# EXT_ADIN.net
KiCad netlist of a schematic drawn in EAGLE
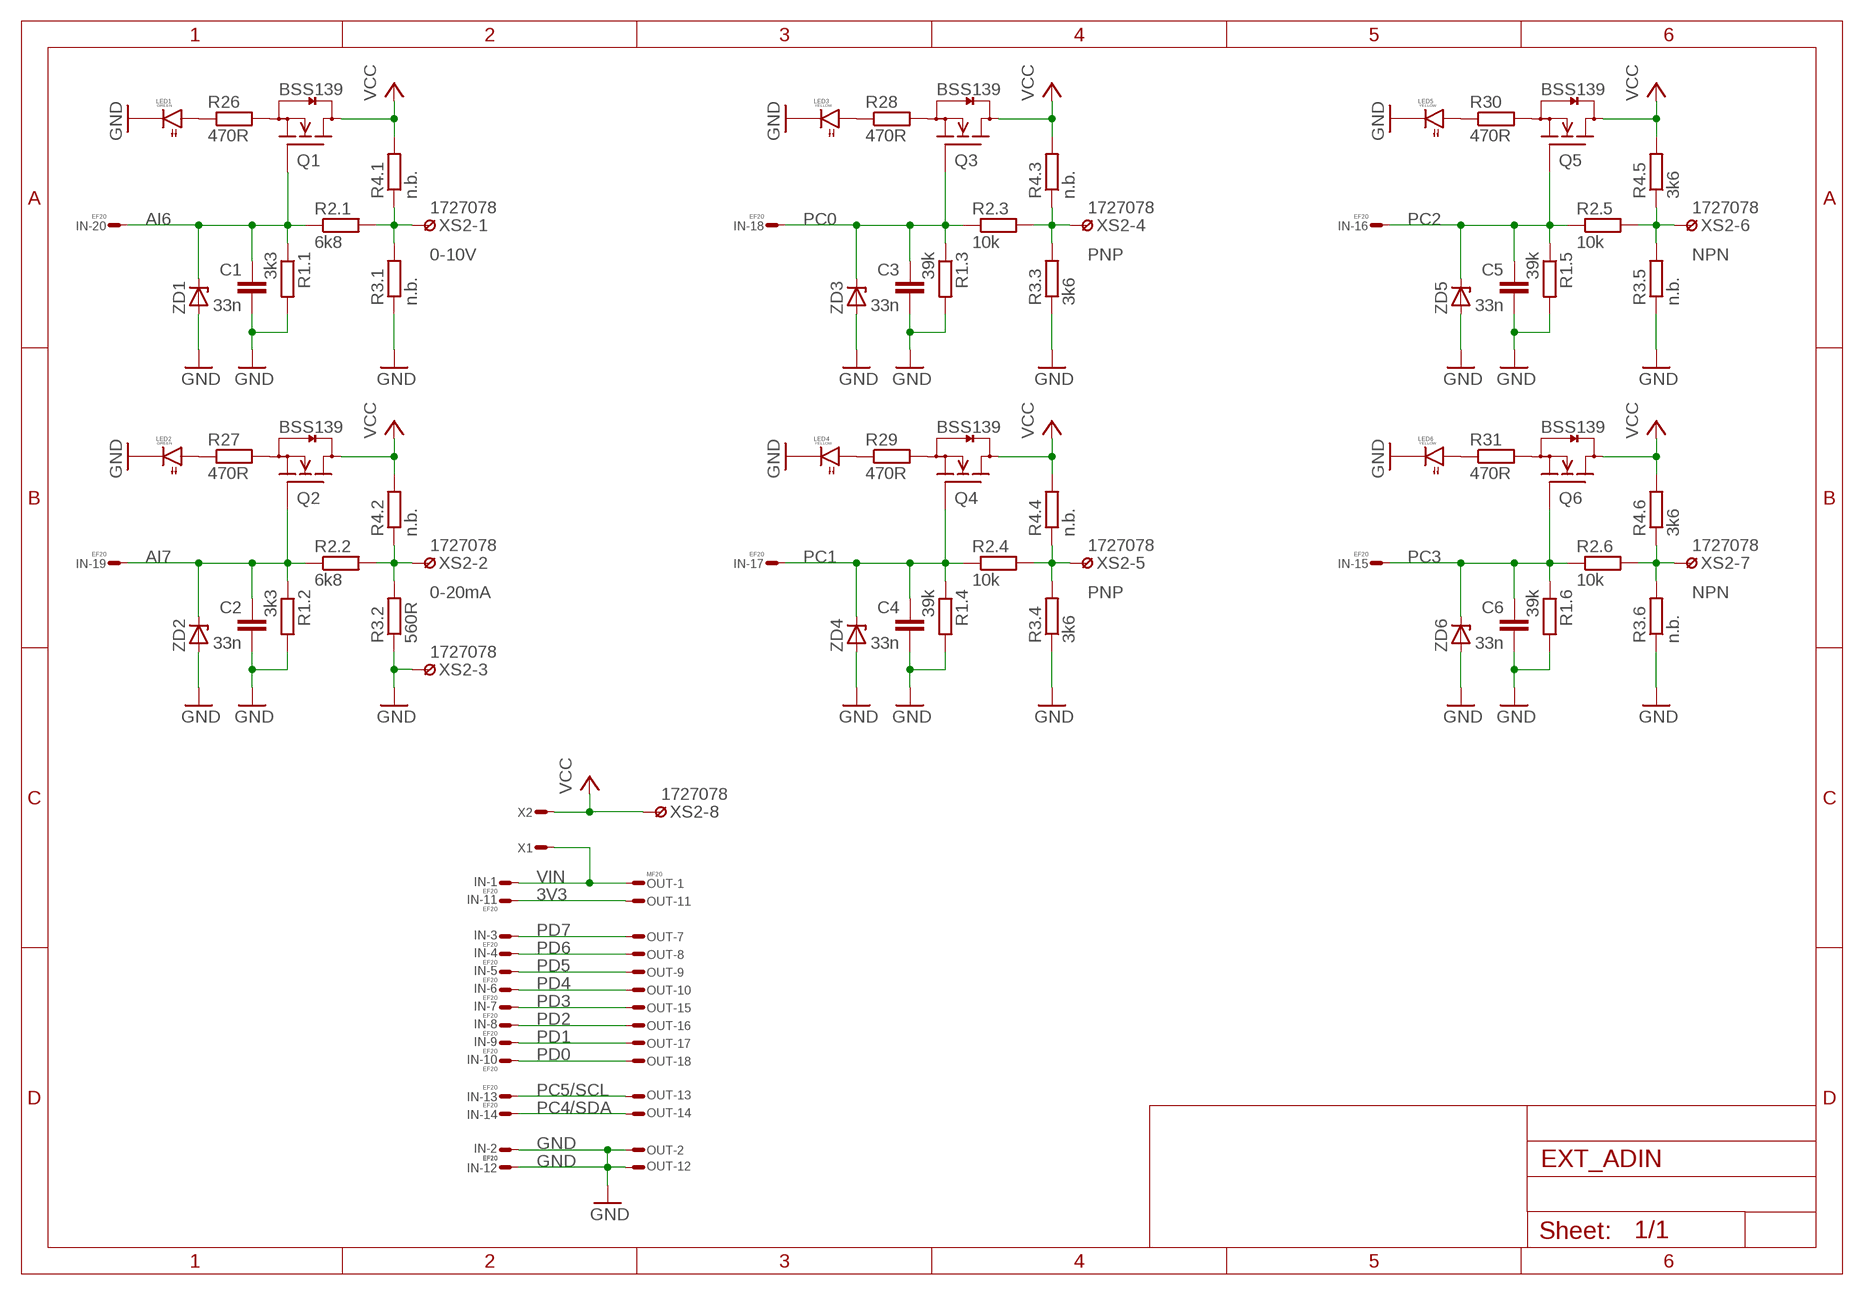
[diagram p0: schematic, sheet 1]

(export (version "E")
  (design (tool "Eeschema 10.0.6"))
  (components
    (comp (ref "C1")
      (value "33n")
      (footprint "eagle-import:1206")
      (libsource (lib "eagle-import") (part "C1206"))
    )
    (comp (ref "C2")
      (value "33n")
      (footprint "eagle-import:1206")
      (libsource (lib "eagle-import") (part "C1206"))
    )
    (comp (ref "C3")
      (value "33n")
      (footprint "eagle-import:1206")
      (libsource (lib "eagle-import") (part "C1206"))
    )
    (comp (ref "C4")
      (value "33n")
      (footprint "eagle-import:1206")
      (libsource (lib "eagle-import") (part "C1206"))
    )
    (comp (ref "C5")
      (value "33n")
      (footprint "eagle-import:1206")
      (libsource (lib "eagle-import") (part "C1206"))
    )
    (comp (ref "C6")
      (value "33n")
      (footprint "eagle-import:1206")
      (libsource (lib "eagle-import") (part "C1206"))
    )
    (comp (ref "IN")
      (value "EF20")
      (footprint "eagle-import:FE10-2WS")
      (libsource (lib "eagle-import") (part "FE20ELS"))
    )
    (comp (ref "LED1")
      (value "GREEN")
      (footprint "eagle-import:1206")
      (libsource (lib "eagle-import") (part "LED1206"))
    )
    (comp (ref "LED2")
      (value "GREEN")
      (footprint "eagle-import:1206")
      (libsource (lib "eagle-import") (part "LED1206"))
    )
    (comp (ref "LED3")
      (value "YELLOW")
      (footprint "eagle-import:1206")
      (libsource (lib "eagle-import") (part "LED1206"))
    )
    (comp (ref "LED4")
      (value "YELLOW")
      (footprint "eagle-import:1206")
      (libsource (lib "eagle-import") (part "LED1206"))
    )
    (comp (ref "LED5")
      (value "YELLOW")
      (footprint "eagle-import:1206")
      (libsource (lib "eagle-import") (part "LED1206"))
    )
    (comp (ref "LED6")
      (value "YELLOW")
      (footprint "eagle-import:1206")
      (libsource (lib "eagle-import") (part "LED1206"))
    )
    (comp (ref "OUT")
      (value "MF20")
      (footprint "eagle-import:ML20LS")
      (libsource (lib "eagle-import") (part "ML20?ELS"))
    )
    (comp (ref "Q1")
      (value "BSS139")
      (footprint "eagle-import:SOT23")
      (libsource (lib "eagle-import") (part "FET-ND23"))
    )
    (comp (ref "Q2")
      (value "BSS139")
      (footprint "eagle-import:SOT23")
      (libsource (lib "eagle-import") (part "FET-ND23"))
    )
    (comp (ref "Q3")
      (value "BSS139")
      (footprint "eagle-import:SOT23")
      (libsource (lib "eagle-import") (part "FET-ND23"))
    )
    (comp (ref "Q4")
      (value "BSS139")
      (footprint "eagle-import:SOT23")
      (libsource (lib "eagle-import") (part "FET-ND23"))
    )
    (comp (ref "Q5")
      (value "BSS139")
      (footprint "eagle-import:SOT23")
      (libsource (lib "eagle-import") (part "FET-ND23"))
    )
    (comp (ref "Q6")
      (value "BSS139")
      (footprint "eagle-import:SOT23")
      (libsource (lib "eagle-import") (part "FET-ND23"))
    )
    (comp (ref "R1.1")
      (value "3k3")
      (footprint "eagle-import:1206")
      (libsource (lib "eagle-import") (part "R1206"))
    )
    (comp (ref "R1.2")
      (value "3k3")
      (footprint "eagle-import:1206")
      (libsource (lib "eagle-import") (part "R1206"))
    )
    (comp (ref "R1.3")
      (value "39k")
      (footprint "eagle-import:1206")
      (libsource (lib "eagle-import") (part "R1206"))
    )
    (comp (ref "R1.4")
      (value "39k")
      (footprint "eagle-import:1206")
      (libsource (lib "eagle-import") (part "R1206"))
    )
    (comp (ref "R1.5")
      (value "39k")
      (footprint "eagle-import:1206")
      (libsource (lib "eagle-import") (part "R1206"))
    )
    (comp (ref "R1.6")
      (value "39k")
      (footprint "eagle-import:1206")
      (libsource (lib "eagle-import") (part "R1206"))
    )
    (comp (ref "R2.1")
      (value "6k8")
      (footprint "eagle-import:1206")
      (libsource (lib "eagle-import") (part "R1206"))
    )
    (comp (ref "R2.2")
      (value "6k8")
      (footprint "eagle-import:1206")
      (libsource (lib "eagle-import") (part "R1206"))
    )
    (comp (ref "R2.3")
      (value "10k")
      (footprint "eagle-import:1206")
      (libsource (lib "eagle-import") (part "R1206"))
    )
    (comp (ref "R2.4")
      (value "10k")
      (footprint "eagle-import:1206")
      (libsource (lib "eagle-import") (part "R1206"))
    )
    (comp (ref "R2.5")
      (value "10k")
      (footprint "eagle-import:1206")
      (libsource (lib "eagle-import") (part "R1206"))
    )
    (comp (ref "R2.6")
      (value "10k")
      (footprint "eagle-import:1206")
      (libsource (lib "eagle-import") (part "R1206"))
    )
    (comp (ref "R3.1")
      (value "n.b.")
      (footprint "eagle-import:1206")
      (libsource (lib "eagle-import") (part "R1206"))
    )
    (comp (ref "R3.2")
      (value "560R")
      (footprint "eagle-import:1206")
      (libsource (lib "eagle-import") (part "R1206"))
    )
    (comp (ref "R3.3")
      (value "3k6")
      (footprint "eagle-import:1206")
      (libsource (lib "eagle-import") (part "R1206"))
    )
    (comp (ref "R3.4")
      (value "3k6")
      (footprint "eagle-import:1206")
      (libsource (lib "eagle-import") (part "R1206"))
    )
    (comp (ref "R3.5")
      (value "n.b.")
      (footprint "eagle-import:1206")
      (libsource (lib "eagle-import") (part "R1206"))
    )
    (comp (ref "R3.6")
      (value "n.b.")
      (footprint "eagle-import:1206")
      (libsource (lib "eagle-import") (part "R1206"))
    )
    (comp (ref "R4.1")
      (value "n.b.")
      (footprint "eagle-import:1206")
      (libsource (lib "eagle-import") (part "R1206"))
    )
    (comp (ref "R4.2")
      (value "n.b.")
      (footprint "eagle-import:1206")
      (libsource (lib "eagle-import") (part "R1206"))
    )
    (comp (ref "R4.3")
      (value "n.b.")
      (footprint "eagle-import:1206")
      (libsource (lib "eagle-import") (part "R1206"))
    )
    (comp (ref "R4.4")
      (value "n.b.")
      (footprint "eagle-import:1206")
      (libsource (lib "eagle-import") (part "R1206"))
    )
    (comp (ref "R4.5")
      (value "3k6")
      (footprint "eagle-import:1206")
      (libsource (lib "eagle-import") (part "R1206"))
    )
    (comp (ref "R4.6")
      (value "3k6")
      (footprint "eagle-import:1206")
      (libsource (lib "eagle-import") (part "R1206"))
    )
    (comp (ref "R26")
      (value "470R")
      (footprint "eagle-import:1206")
      (libsource (lib "eagle-import") (part "R1206"))
    )
    (comp (ref "R27")
      (value "470R")
      (footprint "eagle-import:1206")
      (libsource (lib "eagle-import") (part "R1206"))
    )
    (comp (ref "R28")
      (value "470R")
      (footprint "eagle-import:1206")
      (libsource (lib "eagle-import") (part "R1206"))
    )
    (comp (ref "R29")
      (value "470R")
      (footprint "eagle-import:1206")
      (libsource (lib "eagle-import") (part "R1206"))
    )
    (comp (ref "R30")
      (value "470R")
      (footprint "eagle-import:1206")
      (libsource (lib "eagle-import") (part "R1206"))
    )
    (comp (ref "R31")
      (value "470R")
      (footprint "eagle-import:1206")
      (libsource (lib "eagle-import") (part "R1206"))
    )
    (comp (ref "X1")
      (value "WIREPADT1.6/0.9")
      (footprint "eagle-import:T1.6_0.9")
      (libsource (lib "eagle-import") (part "WIREPADT1.6/0.9"))
    )
    (comp (ref "X2")
      (value "WIREPADT1.6/0.9")
      (footprint "eagle-import:T1.6_0.9")
      (libsource (lib "eagle-import") (part "WIREPADT1.6/0.9"))
    )
    (comp (ref "XS2")
      (value "1727078")
      (footprint "eagle-import:SCR_381_8")
      (libsource (lib "eagle-import") (part "CON8-S"))
    )
    (comp (ref "ZD1")
      (value "ZDSOD80")
      (footprint "eagle-import:SOD80")
      (libsource (lib "eagle-import") (part "ZDSOD80"))
    )
    (comp (ref "ZD2")
      (value "ZDSOD80")
      (footprint "eagle-import:SOD80")
      (libsource (lib "eagle-import") (part "ZDSOD80"))
    )
    (comp (ref "ZD3")
      (value "ZDSOD80")
      (footprint "eagle-import:SOD80")
      (libsource (lib "eagle-import") (part "ZDSOD80"))
    )
    (comp (ref "ZD4")
      (value "ZDSOD80")
      (footprint "eagle-import:SOD80")
      (libsource (lib "eagle-import") (part "ZDSOD80"))
    )
    (comp (ref "ZD5")
      (value "ZDSOD80")
      (footprint "eagle-import:SOD80")
      (libsource (lib "eagle-import") (part "ZDSOD80"))
    )
    (comp (ref "ZD6")
      (value "ZDSOD80")
      (footprint "eagle-import:SOD80")
      (libsource (lib "eagle-import") (part "ZDSOD80"))
    )
  )
  (nets
    (net (code "1") (name "/3V3") (class "Default")
      (node (ref "IN") (pin "P$11") (pinfunction "S_P$11") (pintype "passive"))
      (node (ref "OUT") (pin "P$11") (pinfunction "S_P$11") (pintype "passive"))
    )
    (net (code "2") (name "/AI6") (class "Default")
      (node (ref "C1") (pin "1") (pinfunction "1_1") (pintype "passive"))
      (node (ref "IN") (pin "P$20") (pinfunction "S_P$20") (pintype "passive"))
      (node (ref "Q1") (pin "1") (pinfunction "G_1") (pintype "passive"))
      (node (ref "R1.1") (pin "1") (pinfunction "1_1") (pintype "passive"))
      (node (ref "R2.1") (pin "1") (pinfunction "1_1") (pintype "passive"))
      (node (ref "ZD1") (pin "C") (pinfunction "C_C") (pintype "passive"))
    )
    (net (code "3") (name "/AI7") (class "Default")
      (node (ref "C2") (pin "1") (pinfunction "1_1") (pintype "passive"))
      (node (ref "IN") (pin "P$19") (pinfunction "S_P$19") (pintype "passive"))
      (node (ref "Q2") (pin "1") (pinfunction "G_1") (pintype "passive"))
      (node (ref "R1.2") (pin "1") (pinfunction "1_1") (pintype "passive"))
      (node (ref "R2.2") (pin "1") (pinfunction "1_1") (pintype "passive"))
      (node (ref "ZD2") (pin "C") (pinfunction "C_C") (pintype "passive"))
    )
    (net (code "4") (name "/PC0") (class "Default")
      (node (ref "C3") (pin "1") (pinfunction "1_1") (pintype "passive"))
      (node (ref "IN") (pin "P$18") (pinfunction "S_P$18") (pintype "passive"))
      (node (ref "Q3") (pin "1") (pinfunction "G_1") (pintype "passive"))
      (node (ref "R1.3") (pin "1") (pinfunction "1_1") (pintype "passive"))
      (node (ref "R2.3") (pin "1") (pinfunction "1_1") (pintype "passive"))
      (node (ref "ZD3") (pin "C") (pinfunction "C_C") (pintype "passive"))
    )
    (net (code "5") (name "/PC1") (class "Default")
      (node (ref "C4") (pin "1") (pinfunction "1_1") (pintype "passive"))
      (node (ref "IN") (pin "P$17") (pinfunction "S_P$17") (pintype "passive"))
      (node (ref "Q4") (pin "1") (pinfunction "G_1") (pintype "passive"))
      (node (ref "R1.4") (pin "1") (pinfunction "1_1") (pintype "passive"))
      (node (ref "R2.4") (pin "1") (pinfunction "1_1") (pintype "passive"))
      (node (ref "ZD4") (pin "C") (pinfunction "C_C") (pintype "passive"))
    )
    (net (code "6") (name "/PC2") (class "Default")
      (node (ref "C5") (pin "1") (pinfunction "1_1") (pintype "passive"))
      (node (ref "IN") (pin "P$16") (pinfunction "S_P$16") (pintype "passive"))
      (node (ref "Q5") (pin "1") (pinfunction "G_1") (pintype "passive"))
      (node (ref "R1.5") (pin "1") (pinfunction "1_1") (pintype "passive"))
      (node (ref "R2.5") (pin "1") (pinfunction "1_1") (pintype "passive"))
      (node (ref "ZD5") (pin "C") (pinfunction "C_C") (pintype "passive"))
    )
    (net (code "7") (name "/PC3") (class "Default")
      (node (ref "C6") (pin "1") (pinfunction "1_1") (pintype "passive"))
      (node (ref "IN") (pin "P$15") (pinfunction "S_P$15") (pintype "passive"))
      (node (ref "Q6") (pin "1") (pinfunction "G_1") (pintype "passive"))
      (node (ref "R1.6") (pin "1") (pinfunction "1_1") (pintype "passive"))
      (node (ref "R2.6") (pin "1") (pinfunction "1_1") (pintype "passive"))
      (node (ref "ZD6") (pin "C") (pinfunction "C_C") (pintype "passive"))
    )
    (net (code "8") (name "/PC4{slash}SDA") (class "Default")
      (node (ref "IN") (pin "P$14") (pinfunction "S_P$14") (pintype "passive"))
      (node (ref "OUT") (pin "P$14") (pinfunction "S_P$14") (pintype "passive"))
    )
    (net (code "9") (name "/PC5{slash}SCL") (class "Default")
      (node (ref "IN") (pin "P$13") (pinfunction "S_P$13") (pintype "passive"))
      (node (ref "OUT") (pin "P$13") (pinfunction "S_P$13") (pintype "passive"))
    )
    (net (code "10") (name "/PD0") (class "Default")
      (node (ref "IN") (pin "P$10") (pinfunction "S_P$10") (pintype "passive"))
      (node (ref "OUT") (pin "P$18") (pinfunction "S_P$18") (pintype "passive"))
    )
    (net (code "11") (name "/PD1") (class "Default")
      (node (ref "IN") (pin "P$9") (pinfunction "S_P$9") (pintype "passive"))
      (node (ref "OUT") (pin "P$17") (pinfunction "S_P$17") (pintype "passive"))
    )
    (net (code "12") (name "/PD2") (class "Default")
      (node (ref "IN") (pin "P$8") (pinfunction "S_P$8") (pintype "passive"))
      (node (ref "OUT") (pin "P$16") (pinfunction "S_P$16") (pintype "passive"))
    )
    (net (code "13") (name "/PD3") (class "Default")
      (node (ref "IN") (pin "P$7") (pinfunction "S_P$7") (pintype "passive"))
      (node (ref "OUT") (pin "P$15") (pinfunction "S_P$15") (pintype "passive"))
    )
    (net (code "14") (name "/PD4") (class "Default")
      (node (ref "IN") (pin "P$6") (pinfunction "S_P$6") (pintype "passive"))
      (node (ref "OUT") (pin "P$10") (pinfunction "S_P$10") (pintype "passive"))
    )
    (net (code "15") (name "/PD5") (class "Default")
      (node (ref "IN") (pin "P$5") (pinfunction "S_P$5") (pintype "passive"))
      (node (ref "OUT") (pin "P$9") (pinfunction "S_P$9") (pintype "passive"))
    )
    (net (code "16") (name "/PD6") (class "Default")
      (node (ref "IN") (pin "P$4") (pinfunction "S_P$4") (pintype "passive"))
      (node (ref "OUT") (pin "P$8") (pinfunction "S_P$8") (pintype "passive"))
    )
    (net (code "17") (name "/PD7") (class "Default")
      (node (ref "IN") (pin "P$3") (pinfunction "S_P$3") (pintype "passive"))
      (node (ref "OUT") (pin "P$7") (pinfunction "S_P$7") (pintype "passive"))
    )
    (net (code "18") (name "/VIN") (class "Default")
      (node (ref "IN") (pin "P$1") (pinfunction "S_P$1") (pintype "passive"))
      (node (ref "OUT") (pin "P$1") (pinfunction "S_P$1") (pintype "passive"))
      (node (ref "X1") (pin "1") (pinfunction "S_1") (pintype "passive"))
    )
    (net (code "19") (name "GND") (class "Default")
      (node (ref "C1") (pin "2") (pinfunction "2_2") (pintype "passive"))
      (node (ref "C2") (pin "2") (pinfunction "2_2") (pintype "passive"))
      (node (ref "C3") (pin "2") (pinfunction "2_2") (pintype "passive"))
      (node (ref "C4") (pin "2") (pinfunction "2_2") (pintype "passive"))
      (node (ref "C5") (pin "2") (pinfunction "2_2") (pintype "passive"))
      (node (ref "C6") (pin "2") (pinfunction "2_2") (pintype "passive"))
      (node (ref "IN") (pin "P$12") (pinfunction "S_P$12") (pintype "passive"))
      (node (ref "IN") (pin "P$2") (pinfunction "S_P$2") (pintype "passive"))
      (node (ref "LED1") (pin "2") (pinfunction "C_2") (pintype "bidirectional"))
      (node (ref "LED2") (pin "2") (pinfunction "C_2") (pintype "bidirectional"))
      (node (ref "LED3") (pin "2") (pinfunction "C_2") (pintype "bidirectional"))
      (node (ref "LED4") (pin "2") (pinfunction "C_2") (pintype "bidirectional"))
      (node (ref "LED5") (pin "2") (pinfunction "C_2") (pintype "bidirectional"))
      (node (ref "LED6") (pin "2") (pinfunction "C_2") (pintype "bidirectional"))
      (node (ref "OUT") (pin "P$12") (pinfunction "S_P$12") (pintype "passive"))
      (node (ref "OUT") (pin "P$2") (pinfunction "S_P$2") (pintype "passive"))
      (node (ref "R1.1") (pin "2") (pinfunction "2_2") (pintype "passive"))
      (node (ref "R1.2") (pin "2") (pinfunction "2_2") (pintype "passive"))
      (node (ref "R1.3") (pin "2") (pinfunction "2_2") (pintype "passive"))
      (node (ref "R1.4") (pin "2") (pinfunction "2_2") (pintype "passive"))
      (node (ref "R1.5") (pin "2") (pinfunction "2_2") (pintype "passive"))
      (node (ref "R1.6") (pin "2") (pinfunction "2_2") (pintype "passive"))
      (node (ref "R3.1") (pin "1") (pinfunction "1_1") (pintype "passive"))
      (node (ref "R3.2") (pin "1") (pinfunction "1_1") (pintype "passive"))
      (node (ref "R3.3") (pin "1") (pinfunction "1_1") (pintype "passive"))
      (node (ref "R3.4") (pin "1") (pinfunction "1_1") (pintype "passive"))
      (node (ref "R3.5") (pin "1") (pinfunction "1_1") (pintype "passive"))
      (node (ref "R3.6") (pin "1") (pinfunction "1_1") (pintype "passive"))
      (node (ref "XS2") (pin "P$3") (pinfunction "K_P$3") (pintype "passive"))
      (node (ref "ZD1") (pin "A") (pinfunction "A_A") (pintype "passive"))
      (node (ref "ZD2") (pin "A") (pinfunction "A_A") (pintype "passive"))
      (node (ref "ZD3") (pin "A") (pinfunction "A_A") (pintype "passive"))
      (node (ref "ZD4") (pin "A") (pinfunction "A_A") (pintype "passive"))
      (node (ref "ZD5") (pin "A") (pinfunction "A_A") (pintype "passive"))
      (node (ref "ZD6") (pin "A") (pinfunction "A_A") (pintype "passive"))
    )
    (net (code "20") (name "Net-(LED1-A)") (class "Default")
      (node (ref "LED1") (pin "1") (pinfunction "A_1") (pintype "bidirectional"))
      (node (ref "R26") (pin "1") (pinfunction "1_1") (pintype "passive"))
    )
    (net (code "21") (name "Net-(LED2-A)") (class "Default")
      (node (ref "LED2") (pin "1") (pinfunction "A_1") (pintype "bidirectional"))
      (node (ref "R27") (pin "1") (pinfunction "1_1") (pintype "passive"))
    )
    (net (code "22") (name "Net-(LED3-A)") (class "Default")
      (node (ref "LED3") (pin "1") (pinfunction "A_1") (pintype "bidirectional"))
      (node (ref "R28") (pin "1") (pinfunction "1_1") (pintype "passive"))
    )
    (net (code "23") (name "Net-(LED4-A)") (class "Default")
      (node (ref "LED4") (pin "1") (pinfunction "A_1") (pintype "bidirectional"))
      (node (ref "R29") (pin "1") (pinfunction "1_1") (pintype "passive"))
    )
    (net (code "24") (name "Net-(LED5-A)") (class "Default")
      (node (ref "LED5") (pin "1") (pinfunction "A_1") (pintype "bidirectional"))
      (node (ref "R30") (pin "1") (pinfunction "1_1") (pintype "passive"))
    )
    (net (code "25") (name "Net-(LED6-A)") (class "Default")
      (node (ref "LED6") (pin "1") (pinfunction "A_1") (pintype "bidirectional"))
      (node (ref "R31") (pin "1") (pinfunction "1_1") (pintype "passive"))
    )
    (net (code "26") (name "Net-(Q1-S)") (class "Default")
      (node (ref "Q1") (pin "2") (pinfunction "S_2") (pintype "passive"))
      (node (ref "R26") (pin "2") (pinfunction "2_2") (pintype "passive"))
    )
    (net (code "27") (name "Net-(Q2-S)") (class "Default")
      (node (ref "Q2") (pin "2") (pinfunction "S_2") (pintype "passive"))
      (node (ref "R27") (pin "2") (pinfunction "2_2") (pintype "passive"))
    )
    (net (code "28") (name "Net-(Q3-S)") (class "Default")
      (node (ref "Q3") (pin "2") (pinfunction "S_2") (pintype "passive"))
      (node (ref "R28") (pin "2") (pinfunction "2_2") (pintype "passive"))
    )
    (net (code "29") (name "Net-(Q4-S)") (class "Default")
      (node (ref "Q4") (pin "2") (pinfunction "S_2") (pintype "passive"))
      (node (ref "R29") (pin "2") (pinfunction "2_2") (pintype "passive"))
    )
    (net (code "30") (name "Net-(Q5-S)") (class "Default")
      (node (ref "Q5") (pin "2") (pinfunction "S_2") (pintype "passive"))
      (node (ref "R30") (pin "2") (pinfunction "2_2") (pintype "passive"))
    )
    (net (code "31") (name "Net-(Q6-S)") (class "Default")
      (node (ref "Q6") (pin "2") (pinfunction "S_2") (pintype "passive"))
      (node (ref "R31") (pin "2") (pinfunction "2_2") (pintype "passive"))
    )
    (net (code "32") (name "Net-(XS2A-K)") (class "Default")
      (node (ref "R2.1") (pin "2") (pinfunction "2_2") (pintype "passive"))
      (node (ref "R3.1") (pin "2") (pinfunction "2_2") (pintype "passive"))
      (node (ref "R4.1") (pin "1") (pinfunction "1_1") (pintype "passive"))
      (node (ref "XS2") (pin "P$1") (pinfunction "K_P$1") (pintype "passive"))
    )
    (net (code "33") (name "Net-(XS2B-K)") (class "Default")
      (node (ref "R2.2") (pin "2") (pinfunction "2_2") (pintype "passive"))
      (node (ref "R3.2") (pin "2") (pinfunction "2_2") (pintype "passive"))
      (node (ref "R4.2") (pin "1") (pinfunction "1_1") (pintype "passive"))
      (node (ref "XS2") (pin "P$2") (pinfunction "K_P$2") (pintype "passive"))
    )
    (net (code "34") (name "Net-(XS2D-K)") (class "Default")
      (node (ref "R2.3") (pin "2") (pinfunction "2_2") (pintype "passive"))
      (node (ref "R3.3") (pin "2") (pinfunction "2_2") (pintype "passive"))
      (node (ref "R4.3") (pin "1") (pinfunction "1_1") (pintype "passive"))
      (node (ref "XS2") (pin "P$4") (pinfunction "K_P$4") (pintype "passive"))
    )
    (net (code "35") (name "Net-(XS2E-K)") (class "Default")
      (node (ref "R2.4") (pin "2") (pinfunction "2_2") (pintype "passive"))
      (node (ref "R3.4") (pin "2") (pinfunction "2_2") (pintype "passive"))
      (node (ref "R4.4") (pin "1") (pinfunction "1_1") (pintype "passive"))
      (node (ref "XS2") (pin "P$5") (pinfunction "K_P$5") (pintype "passive"))
    )
    (net (code "36") (name "Net-(XS2F-K)") (class "Default")
      (node (ref "R2.5") (pin "2") (pinfunction "2_2") (pintype "passive"))
      (node (ref "R3.5") (pin "2") (pinfunction "2_2") (pintype "passive"))
      (node (ref "R4.5") (pin "1") (pinfunction "1_1") (pintype "passive"))
      (node (ref "XS2") (pin "P$6") (pinfunction "K_P$6") (pintype "passive"))
    )
    (net (code "37") (name "Net-(XS2G-K)") (class "Default")
      (node (ref "R2.6") (pin "2") (pinfunction "2_2") (pintype "passive"))
      (node (ref "R3.6") (pin "2") (pinfunction "2_2") (pintype "passive"))
      (node (ref "R4.6") (pin "1") (pinfunction "1_1") (pintype "passive"))
      (node (ref "XS2") (pin "P$7") (pinfunction "K_P$7") (pintype "passive"))
    )
    (net (code "38") (name "VCC") (class "Default")
      (node (ref "Q1") (pin "3") (pinfunction "D_3") (pintype "passive"))
      (node (ref "Q2") (pin "3") (pinfunction "D_3") (pintype "passive"))
      (node (ref "Q3") (pin "3") (pinfunction "D_3") (pintype "passive"))
      (node (ref "Q4") (pin "3") (pinfunction "D_3") (pintype "passive"))
      (node (ref "Q5") (pin "3") (pinfunction "D_3") (pintype "passive"))
      (node (ref "Q6") (pin "3") (pinfunction "D_3") (pintype "passive"))
      (node (ref "R4.1") (pin "2") (pinfunction "2_2") (pintype "passive"))
      (node (ref "R4.2") (pin "2") (pinfunction "2_2") (pintype "passive"))
      (node (ref "R4.3") (pin "2") (pinfunction "2_2") (pintype "passive"))
      (node (ref "R4.4") (pin "2") (pinfunction "2_2") (pintype "passive"))
      (node (ref "R4.5") (pin "2") (pinfunction "2_2") (pintype "passive"))
      (node (ref "R4.6") (pin "2") (pinfunction "2_2") (pintype "passive"))
      (node (ref "X2") (pin "1") (pinfunction "S_1") (pintype "passive"))
      (node (ref "XS2") (pin "P$8") (pinfunction "K_P$8") (pintype "passive"))
    )
  )
)
